# optoserial.net
KiCad netlist of a schematic drawn in EAGLE
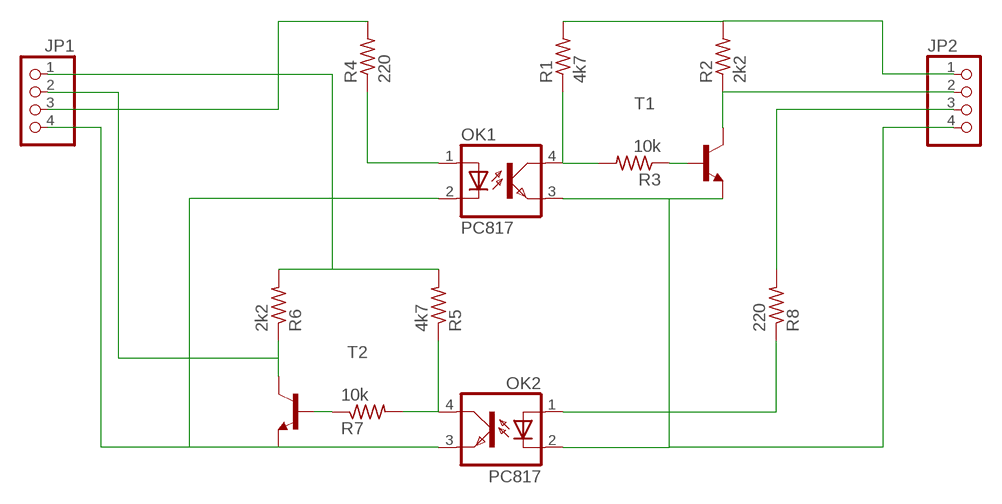
[diagram p0: schematic, sheet 1]

(export (version "E")
  (design (tool "Eeschema 10.0.6"))
  (components
    (comp (ref "JP1")
      (value "PINHD-1X4")
      (footprint "eagle-import:1X04")
      (libsource (lib "eagle-import") (part "PINHD-1X4"))
    )
    (comp (ref "JP2")
      (value "PINHD-1X4")
      (footprint "eagle-import:1X04")
      (libsource (lib "eagle-import") (part "PINHD-1X4"))
    )
    (comp (ref "OK1")
      (value "PC817")
      (footprint "eagle-import:DIL04")
      (fields (field (name "MPN") "PC817X4J000F"))
      (libsource (lib "eagle-import") (part "PC817"))
    )
    (comp (ref "OK2")
      (value "PC817")
      (footprint "eagle-import:DIL04")
      (fields (field (name "MPN") "PC817X4J000F"))
      (libsource (lib "eagle-import") (part "PC817"))
    )
    (comp (ref "R1")
      (value "4k7")
      (footprint "eagle-import:0207_10")
      (libsource (lib "eagle-import") (part "R-US_0207/10"))
    )
    (comp (ref "R2")
      (value "2k2")
      (footprint "eagle-import:0207_10")
      (libsource (lib "eagle-import") (part "R-US_0207/10"))
    )
    (comp (ref "R3")
      (value "10k")
      (footprint "eagle-import:0207_10")
      (libsource (lib "eagle-import") (part "R-US_0207/10"))
    )
    (comp (ref "R4")
      (value "220")
      (footprint "eagle-import:0207_10")
      (libsource (lib "eagle-import") (part "R-US_0207/10"))
    )
    (comp (ref "R5")
      (value "4k7")
      (footprint "eagle-import:0207_10")
      (libsource (lib "eagle-import") (part "R-US_0207/10"))
    )
    (comp (ref "R6")
      (value "2k2")
      (footprint "eagle-import:0207_10")
      (libsource (lib "eagle-import") (part "R-US_0207/10"))
    )
    (comp (ref "R7")
      (value "10k")
      (footprint "eagle-import:0207_10")
      (libsource (lib "eagle-import") (part "R-US_0207/10"))
    )
    (comp (ref "R8")
      (value "220")
      (footprint "eagle-import:0207_10")
      (libsource (lib "eagle-import") (part "R-US_0207/10"))
    )
    (comp (ref "T1")
      (value "2N2222-NPN-TO92-EBC")
      (footprint "eagle-import:TO92-EBC")
      (libsource (lib "eagle-import") (part "-NPN-TO92-EBC2N2222"))
    )
    (comp (ref "T2")
      (value "2N2222-NPN-TO92-EBC")
      (footprint "eagle-import:TO92-EBC")
      (libsource (lib "eagle-import") (part "-NPN-TO92-EBC2N2222"))
    )
  )
  (nets
    (net (code "1") (name "Net-(JP1-Pad1)") (class "Default")
      (node (ref "JP1") (pin "1") (pinfunction "1_1") (pintype "passive"))
      (node (ref "R5") (pin "2") (pinfunction "2_2") (pintype "passive"))
      (node (ref "R6") (pin "2") (pinfunction "2_2") (pintype "passive"))
    )
    (net (code "2") (name "Net-(JP1-Pad2)") (class "Default")
      (node (ref "JP1") (pin "2") (pinfunction "2_2") (pintype "passive"))
      (node (ref "R6") (pin "1") (pinfunction "1_1") (pintype "passive"))
      (node (ref "T2") (pin "C") (pinfunction "C_C") (pintype "passive"))
    )
    (net (code "3") (name "Net-(JP1-Pad3)") (class "Default")
      (node (ref "JP1") (pin "3") (pinfunction "3_3") (pintype "passive"))
      (node (ref "R4") (pin "2") (pinfunction "2_2") (pintype "passive"))
    )
    (net (code "4") (name "Net-(JP2-Pad1)") (class "Default")
      (node (ref "JP2") (pin "1") (pinfunction "1_1") (pintype "passive"))
      (node (ref "R1") (pin "2") (pinfunction "2_2") (pintype "passive"))
      (node (ref "R2") (pin "2") (pinfunction "2_2") (pintype "passive"))
    )
    (net (code "5") (name "Net-(JP2-Pad2)") (class "Default")
      (node (ref "JP2") (pin "2") (pinfunction "2_2") (pintype "passive"))
      (node (ref "R2") (pin "1") (pinfunction "1_1") (pintype "passive"))
      (node (ref "T1") (pin "C") (pinfunction "C_C") (pintype "passive"))
    )
    (net (code "6") (name "Net-(JP2-Pad3)") (class "Default")
      (node (ref "JP2") (pin "3") (pinfunction "3_3") (pintype "passive"))
      (node (ref "R8") (pin "2") (pinfunction "2_2") (pintype "passive"))
    )
    (net (code "7") (name "Net-(OK1-A)") (class "Default")
      (node (ref "OK1") (pin "1") (pinfunction "A_1") (pintype "passive"))
      (node (ref "R4") (pin "1") (pinfunction "1_1") (pintype "passive"))
    )
    (net (code "8") (name "Net-(OK1-C)") (class "Default")
      (node (ref "JP1") (pin "4") (pinfunction "4_4") (pintype "passive"))
      (node (ref "OK1") (pin "2") (pinfunction "C_2") (pintype "passive"))
      (node (ref "OK2") (pin "3") (pinfunction "EMIT_3") (pintype "passive"))
      (node (ref "T2") (pin "E") (pinfunction "E_E") (pintype "passive"))
    )
    (net (code "9") (name "Net-(OK1-COL)") (class "Default")
      (node (ref "OK1") (pin "4") (pinfunction "COL_4") (pintype "passive"))
      (node (ref "R1") (pin "1") (pinfunction "1_1") (pintype "passive"))
      (node (ref "R3") (pin "2") (pinfunction "2_2") (pintype "passive"))
    )
    (net (code "10") (name "Net-(OK1-EMIT)") (class "Default")
      (node (ref "JP2") (pin "4") (pinfunction "4_4") (pintype "passive"))
      (node (ref "OK1") (pin "3") (pinfunction "EMIT_3") (pintype "passive"))
      (node (ref "OK2") (pin "2") (pinfunction "C_2") (pintype "passive"))
      (node (ref "T1") (pin "E") (pinfunction "E_E") (pintype "passive"))
    )
    (net (code "11") (name "Net-(OK2-A)") (class "Default")
      (node (ref "OK2") (pin "1") (pinfunction "A_1") (pintype "passive"))
      (node (ref "R8") (pin "1") (pinfunction "1_1") (pintype "passive"))
    )
    (net (code "12") (name "Net-(OK2-COL)") (class "Default")
      (node (ref "OK2") (pin "4") (pinfunction "COL_4") (pintype "passive"))
      (node (ref "R5") (pin "1") (pinfunction "1_1") (pintype "passive"))
      (node (ref "R7") (pin "2") (pinfunction "2_2") (pintype "passive"))
    )
    (net (code "13") (name "Net-(R3-Pad1)") (class "Default")
      (node (ref "R3") (pin "1") (pinfunction "1_1") (pintype "passive"))
      (node (ref "T1") (pin "B") (pinfunction "B_B") (pintype "passive"))
    )
    (net (code "14") (name "Net-(R7-Pad1)") (class "Default")
      (node (ref "R7") (pin "1") (pinfunction "1_1") (pintype "passive"))
      (node (ref "T2") (pin "B") (pinfunction "B_B") (pintype "passive"))
    )
  )
)
